# ADC_part2.net
KiCad netlist of a schematic drawn in Altium Designer
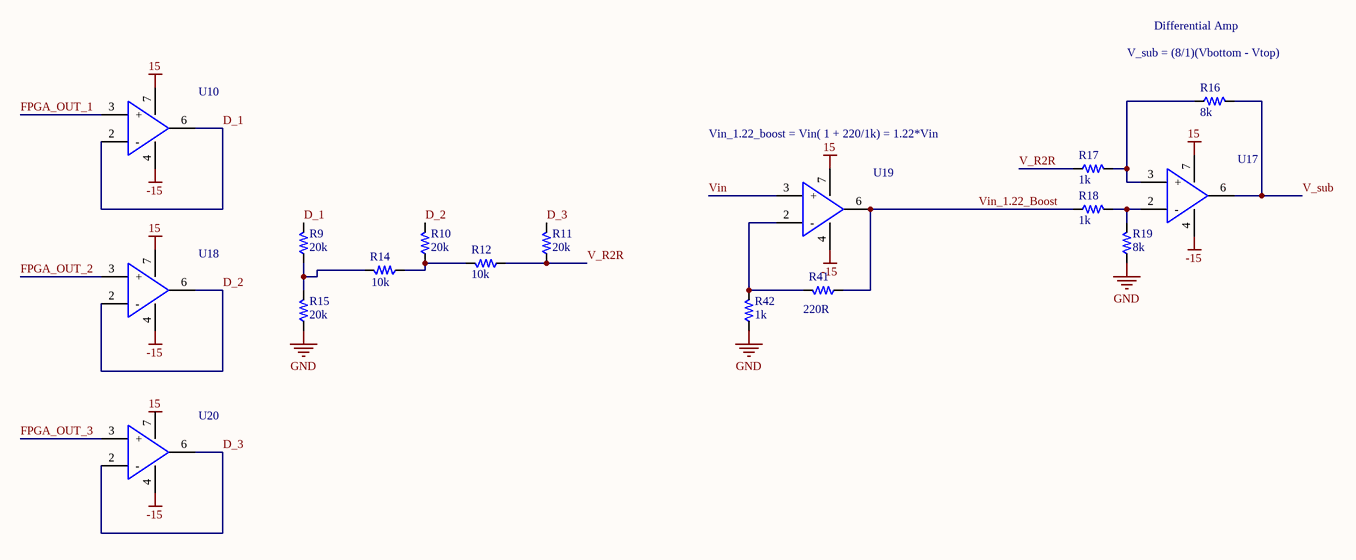
[diagram p0: ADC_part2.SchDoc]

(export (version "E")
  (design (tool "Eeschema 10.0.6"))
  (components
    (comp (ref "R9")
      (value "20k")
      (footprint "PCB_GENERIC_SMD_0603")
      (description "RES 0603 100ohm 5% 63mW")
      (fields (field (name "TOLERANCE") "5%") (field (name "POWER") "63mW"))
      (libsource (lib "RES") (part "R060-00101-05"))
    )
    (comp (ref "R10")
      (value "20k")
      (footprint "PCB_GENERIC_SMD_0603")
      (description "RES 0603 100ohm 5% 63mW")
      (fields (field (name "TOLERANCE") "5%") (field (name "POWER") "63mW"))
      (libsource (lib "RES") (part "R060-00101-05"))
    )
    (comp (ref "R11")
      (value "20k")
      (footprint "PCB_GENERIC_SMD_0603")
      (description "RES 0603 100ohm 5% 63mW")
      (fields (field (name "TOLERANCE") "5%") (field (name "POWER") "63mW"))
      (libsource (lib "RES") (part "R060-00101-05"))
    )
    (comp (ref "R12")
      (value "10k")
      (footprint "PCB_GENERIC_SMD_0603")
      (description "RES 0603 100ohm 5% 63mW")
      (fields (field (name "TOLERANCE") "5%") (field (name "POWER") "63mW"))
      (libsource (lib "RES") (part "R060-00101-05"))
    )
    (comp (ref "R14")
      (value "10k")
      (footprint "PCB_GENERIC_SMD_0603")
      (description "RES 0603 100ohm 5% 63mW")
      (fields (field (name "TOLERANCE") "5%") (field (name "POWER") "63mW"))
      (libsource (lib "RES") (part "R060-00101-05"))
    )
    (comp (ref "R15")
      (value "20k")
      (footprint "PCB_GENERIC_SMD_0603")
      (description "RES 0603 100ohm 5% 63mW")
      (fields (field (name "TOLERANCE") "5%") (field (name "POWER") "63mW"))
      (libsource (lib "RES") (part "R060-00101-05"))
    )
    (comp (ref "R16")
      (value "8k")
      (footprint "PCB_GENERIC_SMD_0603")
      (description "RES 0603 100ohm 5% 63mW")
      (fields (field (name "TOLERANCE") "5%") (field (name "POWER") "63mW"))
      (libsource (lib "RES") (part "R060-00101-05"))
    )
    (comp (ref "R17")
      (value "1k")
      (footprint "PCB_GENERIC_SMD_0603")
      (description "RES 0603 100ohm 5% 63mW")
      (fields (field (name "TOLERANCE") "5%") (field (name "POWER") "63mW"))
      (libsource (lib "RES") (part "R060-00101-05"))
    )
    (comp (ref "R18")
      (value "1k")
      (footprint "PCB_GENERIC_SMD_0603")
      (description "RES 0603 100ohm 5% 63mW")
      (fields (field (name "TOLERANCE") "5%") (field (name "POWER") "63mW"))
      (libsource (lib "RES") (part "R060-00101-05"))
    )
    (comp (ref "R19")
      (value "8k")
      (footprint "PCB_GENERIC_SMD_0603")
      (description "RES 0603 100ohm 5% 63mW")
      (fields (field (name "TOLERANCE") "5%") (field (name "POWER") "63mW"))
      (libsource (lib "RES") (part "R060-00101-05"))
    )
    (comp (ref "R41")
      (value "220R")
      (footprint "PCB_GENERIC_SMD_0603")
      (description "RES 0603 100ohm 5% 63mW")
      (fields (field (name "TOLERANCE") "5%") (field (name "POWER") "63mW"))
      (libsource (lib "RES") (part "R060-00101-05"))
    )
    (comp (ref "R42")
      (value "1k")
      (footprint "PCB_GENERIC_SMD_0603")
      (description "RES 0603 100ohm 5% 63mW")
      (fields (field (name "TOLERANCE") "5%") (field (name "POWER") "63mW"))
      (libsource (lib "RES") (part "R060-00101-05"))
    )
    (comp (ref "U10")
      (value "AP331A")
      (footprint "SOT95P285X130-5N")
      (description "Single Channel Comparator, Open Drain, SC-74A/SOT-753")
      (libsource (lib "Op_Amp") (part "AP331A"))
    )
    (comp (ref "U17")
      (value "AP331A")
      (footprint "SOT95P285X130-5N")
      (description "Single Channel Comparator, Open Drain, SC-74A/SOT-753")
      (libsource (lib "Op_Amp") (part "AP331A"))
    )
    (comp (ref "U18")
      (value "AP331A")
      (footprint "SOT95P285X130-5N")
      (description "Single Channel Comparator, Open Drain, SC-74A/SOT-753")
      (libsource (lib "Op_Amp") (part "AP331A"))
    )
    (comp (ref "U19")
      (value "AP331A")
      (footprint "SOT95P285X130-5N")
      (description "Single Channel Comparator, Open Drain, SC-74A/SOT-753")
      (libsource (lib "Op_Amp") (part "AP331A"))
    )
    (comp (ref "U20")
      (value "AP331A")
      (footprint "SOT95P285X130-5N")
      (description "Single Channel Comparator, Open Drain, SC-74A/SOT-753")
      (libsource (lib "Op_Amp") (part "AP331A"))
    )
  )
  (nets
    (net (code "1") (name "-15") (class "Default")
      (node (ref "U10") (pin "4") (pinfunction "GND_4") (pintype "passive"))
      (node (ref "U17") (pin "4") (pinfunction "GND_4") (pintype "passive"))
      (node (ref "U18") (pin "4") (pinfunction "GND_4") (pintype "passive"))
      (node (ref "U19") (pin "4") (pinfunction "GND_4") (pintype "passive"))
      (node (ref "U20") (pin "4") (pinfunction "GND_4") (pintype "passive"))
    )
    (net (code "2") (name "/D_1") (class "Default")
      (node (ref "R9") (pin "2") (pinfunction "2_2") (pintype "passive"))
      (node (ref "U10") (pin "2") (pinfunction "-_2") (pintype "passive"))
      (node (ref "U10") (pin "6") (pinfunction "6_6") (pintype "passive"))
    )
    (net (code "3") (name "/D_2") (class "Default")
      (node (ref "R10") (pin "2") (pinfunction "2_2") (pintype "passive"))
      (node (ref "U18") (pin "2") (pinfunction "-_2") (pintype "passive"))
      (node (ref "U18") (pin "6") (pinfunction "6_6") (pintype "passive"))
    )
    (net (code "4") (name "/D_3") (class "Default")
      (node (ref "R11") (pin "2") (pinfunction "2_2") (pintype "passive"))
      (node (ref "U20") (pin "2") (pinfunction "-_2") (pintype "passive"))
      (node (ref "U20") (pin "6") (pinfunction "6_6") (pintype "passive"))
    )
    (net (code "5") (name "/FPGA_OUT_1") (class "Default")
      (node (ref "U10") (pin "3") (pinfunction "+_3") (pintype "passive"))
    )
    (net (code "6") (name "/FPGA_OUT_2") (class "Default")
      (node (ref "U18") (pin "3") (pinfunction "+_3") (pintype "passive"))
    )
    (net (code "7") (name "/FPGA_OUT_3") (class "Default")
      (node (ref "U20") (pin "3") (pinfunction "+_3") (pintype "passive"))
    )
    (net (code "8") (name "/V_R2R") (class "Default")
      (node (ref "R11") (pin "1") (pinfunction "1_1") (pintype "passive"))
      (node (ref "R12") (pin "1") (pinfunction "1_1") (pintype "passive"))
      (node (ref "R17") (pin "1") (pinfunction "1_1") (pintype "passive"))
    )
    (net (code "9") (name "/V_sub") (class "Default")
      (node (ref "R16") (pin "2") (pinfunction "2_2") (pintype "passive"))
      (node (ref "U17") (pin "6") (pinfunction "6_6") (pintype "passive"))
    )
    (net (code "10") (name "/Vin") (class "Default")
      (node (ref "U19") (pin "3") (pinfunction "+_3") (pintype "passive"))
    )
    (net (code "11") (name "/Vin_1.22_Boost") (class "Default")
      (node (ref "R18") (pin "1") (pinfunction "1_1") (pintype "passive"))
      (node (ref "R41") (pin "1") (pinfunction "1_1") (pintype "passive"))
      (node (ref "U19") (pin "6") (pinfunction "6_6") (pintype "passive"))
    )
    (net (code "12") (name "15") (class "Default")
      (node (ref "U10") (pin "7") (pinfunction "VCC_7") (pintype "passive"))
      (node (ref "U17") (pin "7") (pinfunction "VCC_7") (pintype "passive"))
      (node (ref "U18") (pin "7") (pinfunction "VCC_7") (pintype "passive"))
      (node (ref "U19") (pin "7") (pinfunction "VCC_7") (pintype "passive"))
    )
    (net (code "13") (name "GND") (class "Default")
      (node (ref "R15") (pin "1") (pinfunction "1_1") (pintype "passive"))
      (node (ref "R19") (pin "1") (pinfunction "1_1") (pintype "passive"))
      (node (ref "R42") (pin "1") (pinfunction "1_1") (pintype "passive"))
    )
    (net (code "14") (name "Net-(R10-Pad1)") (class "Default")
      (node (ref "R10") (pin "1") (pinfunction "1_1") (pintype "passive"))
      (node (ref "R12") (pin "2") (pinfunction "2_2") (pintype "passive"))
      (node (ref "R14") (pin "1") (pinfunction "1_1") (pintype "passive"))
    )
    (net (code "15") (name "Net-(R14-Pad2)") (class "Default")
      (node (ref "R14") (pin "2") (pinfunction "2_2") (pintype "passive"))
      (node (ref "R15") (pin "2") (pinfunction "2_2") (pintype "passive"))
      (node (ref "R9") (pin "1") (pinfunction "1_1") (pintype "passive"))
    )
    (net (code "16") (name "Net-(U17-+)") (class "Default")
      (node (ref "R16") (pin "1") (pinfunction "1_1") (pintype "passive"))
      (node (ref "R17") (pin "2") (pinfunction "2_2") (pintype "passive"))
      (node (ref "U17") (pin "3") (pinfunction "+_3") (pintype "passive"))
    )
    (net (code "17") (name "Net-(U17--)") (class "Default")
      (node (ref "R18") (pin "2") (pinfunction "2_2") (pintype "passive"))
      (node (ref "R19") (pin "2") (pinfunction "2_2") (pintype "passive"))
      (node (ref "U17") (pin "2") (pinfunction "-_2") (pintype "passive"))
    )
    (net (code "18") (name "Net-(U19--)") (class "Default")
      (node (ref "R41") (pin "2") (pinfunction "2_2") (pintype "passive"))
      (node (ref "R42") (pin "2") (pinfunction "2_2") (pintype "passive"))
      (node (ref "U19") (pin "2") (pinfunction "-_2") (pintype "passive"))
    )
    (net (code "19") (name "unconnected-(U20-VCC-Pad7)") (class "Default")
      (node (ref "U20") (pin "7") (pinfunction "VCC_7") (pintype "passive"))
    )
  )
)
